# Switch.net
KiCad netlist of a schematic drawn in Altium Designer
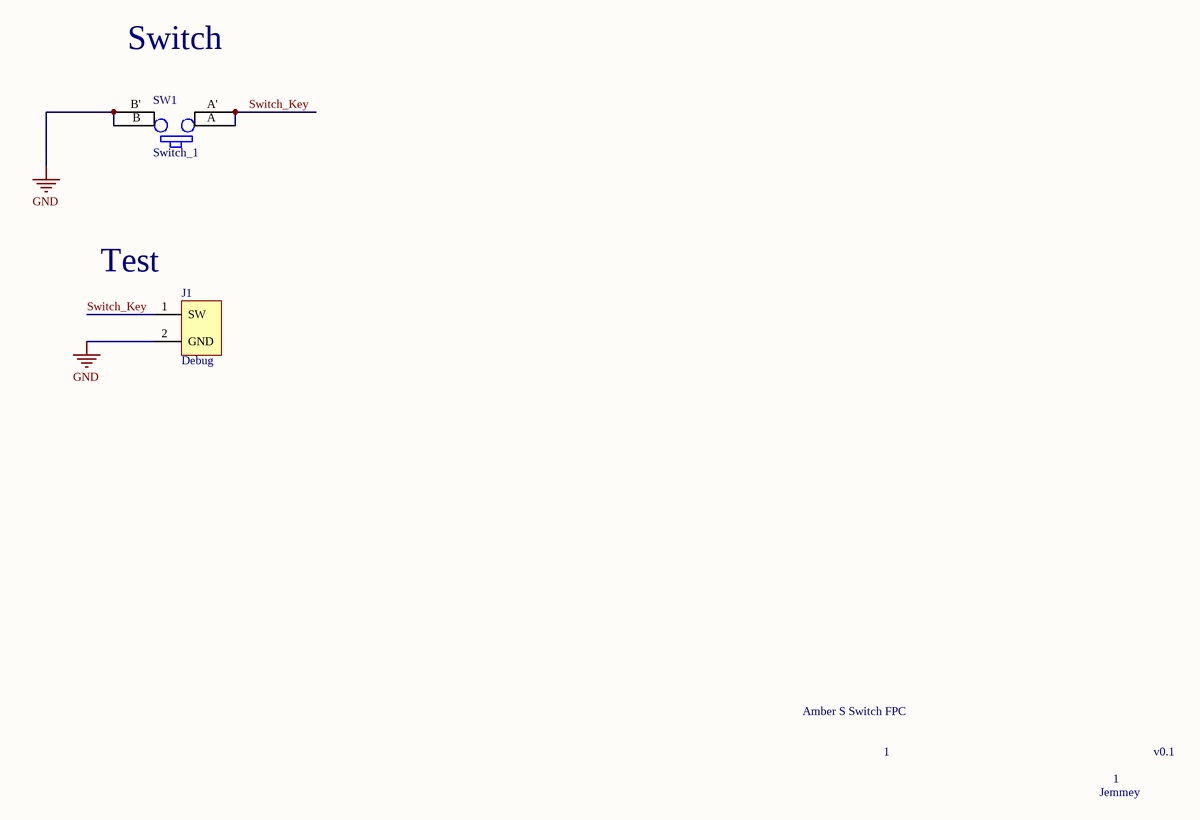
[diagram p0: Switch.SchDoc]

(export (version "E")
  (design (tool "Eeschema 10.0.6"))
  (components
    (comp (ref "J1")
      (value "Debug")
      (footprint "Debug-2Pin")
      (description "厂家：暂定，型号：暂定")
      (libsource (lib "Swtich") (part "Debug_1"))
    )
    (comp (ref "SW1")
      (value "Switch_1")
      (footprint "EVQPLD")
      (description "厂家：松下，型号：EVQPLMA15")
      (libsource (lib "Amber_Display") (part "Switch_1"))
    )
  )
  (nets
    (net (code "1") (name "/Switch_Key") (class "Default")
      (node (ref "J1") (pin "1") (pinfunction "SW_1") (pintype "passive"))
      (node (ref "SW1") (pin "A") (pinfunction "A_A") (pintype "passive"))
      (node (ref "SW1") (pin "A'") (pinfunction "A'_A'") (pintype "passive"))
    )
    (net (code "2") (name "GND") (class "Default")
      (node (ref "J1") (pin "2") (pinfunction "GND_2") (pintype "passive"))
      (node (ref "SW1") (pin "B") (pinfunction "B_B") (pintype "passive"))
      (node (ref "SW1") (pin "B'") (pinfunction "B'_B'") (pintype "passive"))
    )
  )
)
